# ChargerControl.net
KiCad netlist of a schematic drawn in Altium Designer
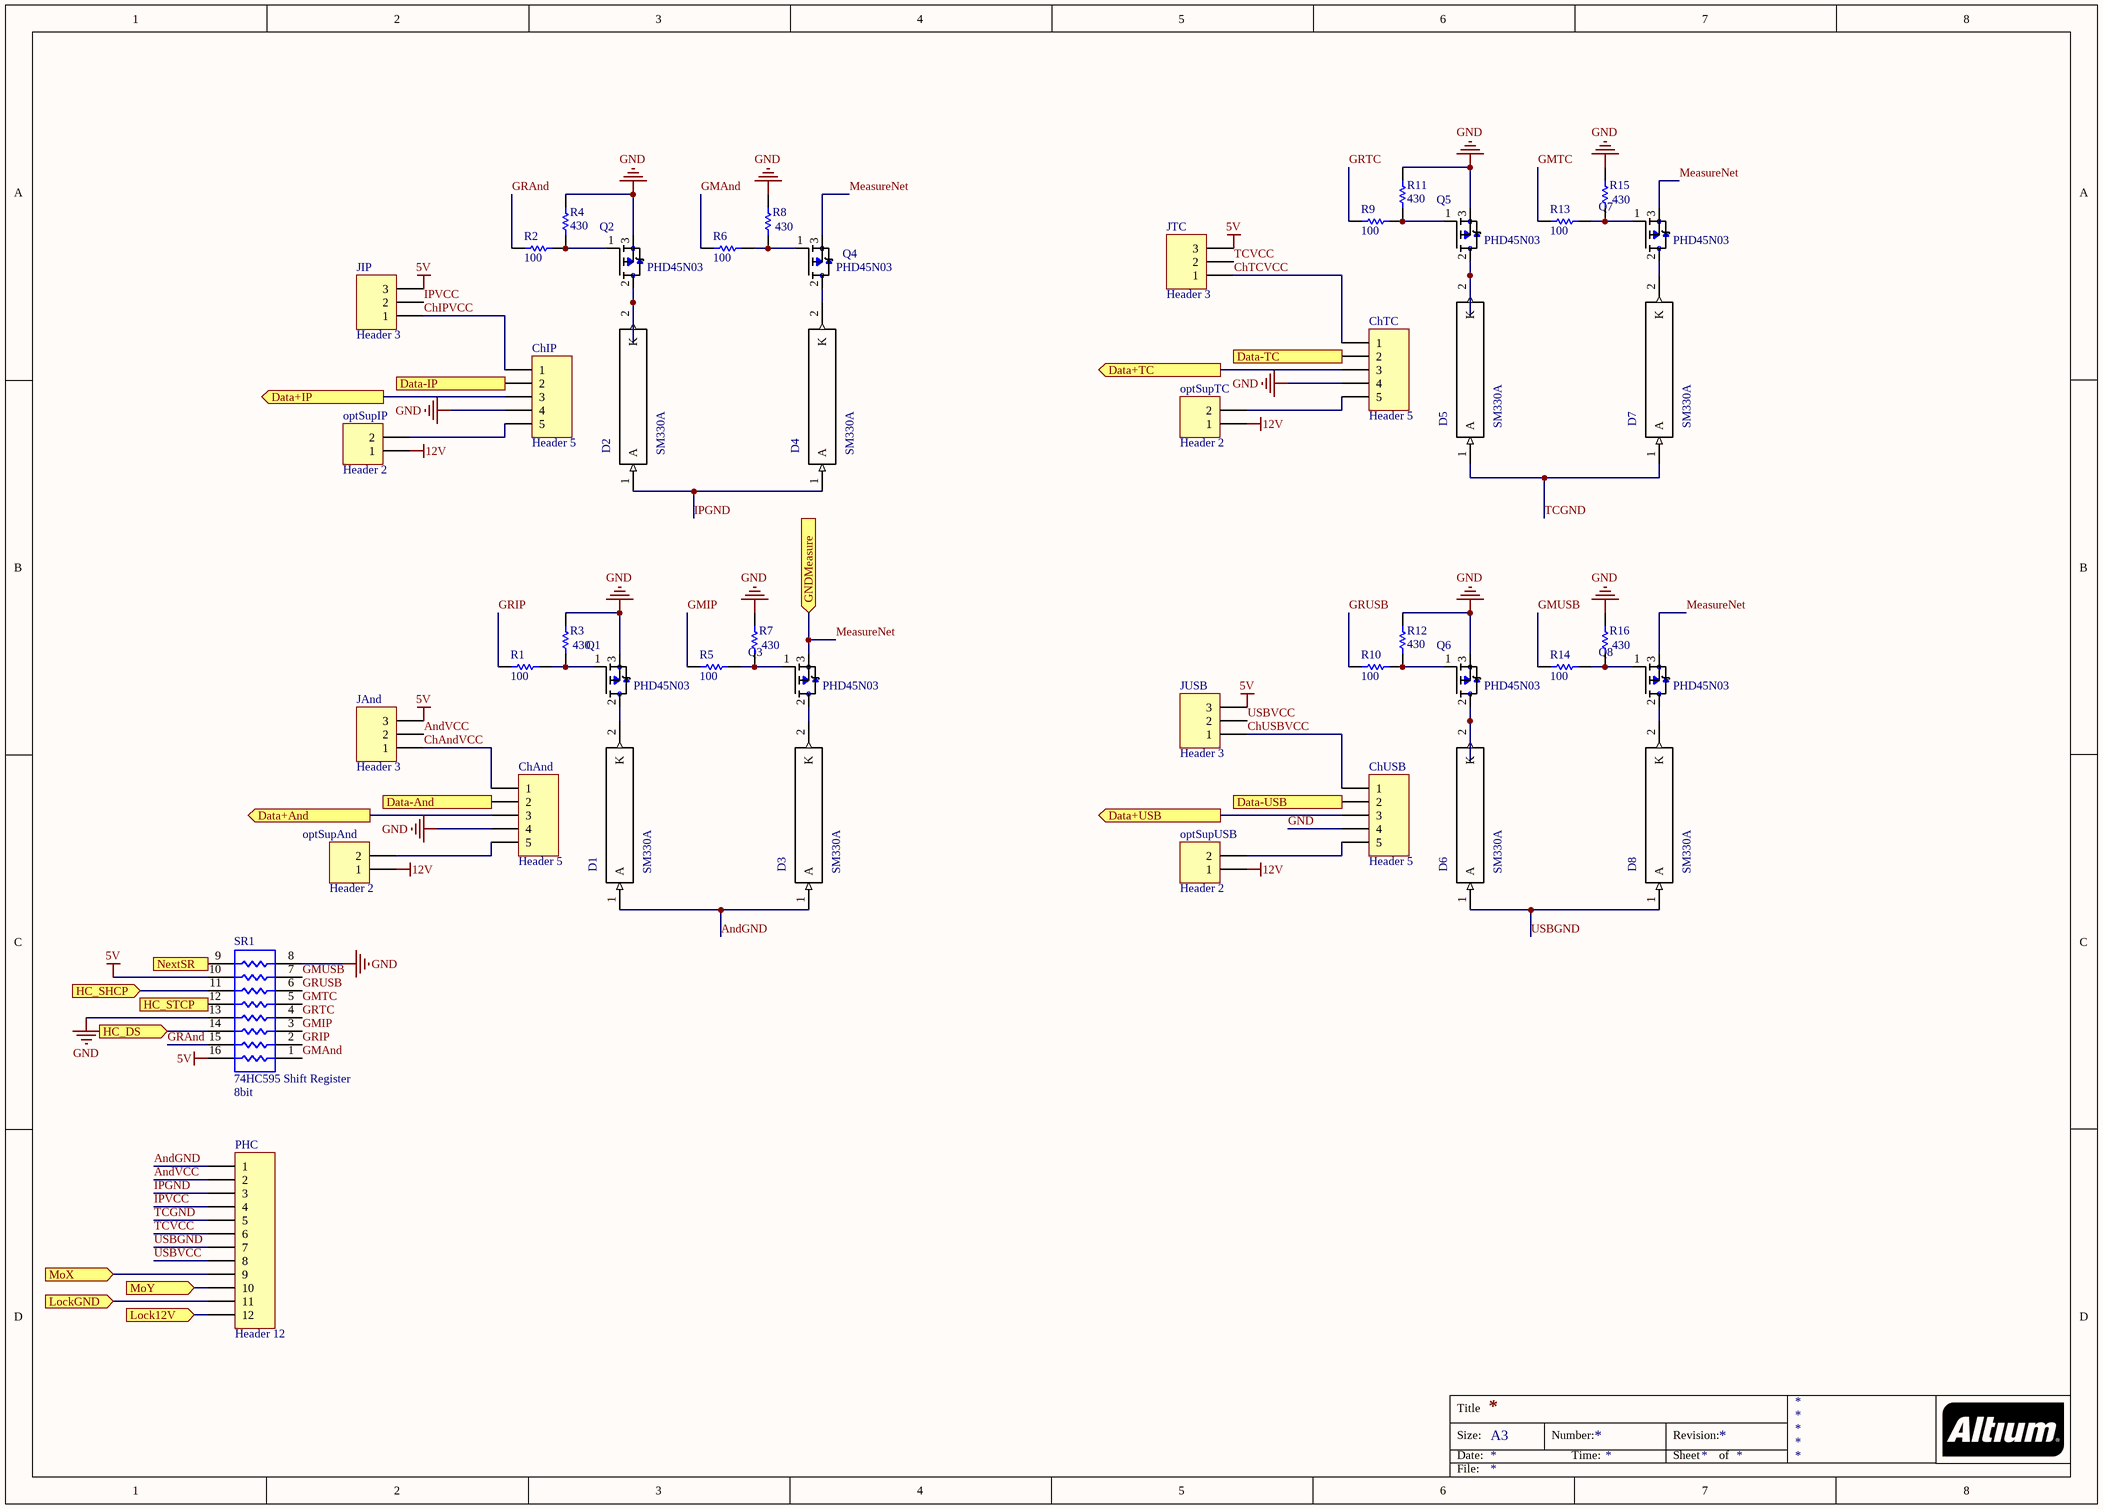
[diagram p0: ChargerControl.SchDoc]

(export (version "E")
  (design (tool "Eeschema 10.0.6"))
  (components
    (comp (ref "ChAnd")
      (value "Header 5")
      (footprint "HDR1X5")
      (description "ورودی از شارژر اندرویید")
      (fields (field (name "PUBLISHER") "Altium Limited"))
      (libsource (lib "Miscellaneous Connectors") (part "Header 5"))
    )
    (comp (ref "ChIP")
      (value "Header 5")
      (footprint "HDR1X5")
      (description "ورودی از شارژر اندرویید")
      (fields (field (name "PUBLISHER") "Altium Limited"))
      (libsource (lib "Miscellaneous Connectors") (part "Header 5"))
    )
    (comp (ref "ChTC")
      (value "Header 5")
      (footprint "HDR1X5")
      (description "ورودی از شارژر اندرویید")
      (fields (field (name "PUBLISHER") "Altium Limited"))
      (libsource (lib "Miscellaneous Connectors") (part "Header 5"))
    )
    (comp (ref "ChUSB")
      (value "Header 5")
      (footprint "HDR1X5")
      (description "ورودی از شارژر اندرویید")
      (fields (field (name "PUBLISHER") "Altium Limited"))
      (libsource (lib "Miscellaneous Connectors") (part "Header 5"))
    )
    (comp (ref "D1")
      (value "SM330A")
      (footprint "*DIOM5227X270N_S1M(Primary)")
      (description "SCHOTTKY RECTIFIER 2A; Voltage Vrrm: 60V; Diode Case Style: DO-214AC; Case Style: DO-214AC")
      (fields (field (name "MF") "STMicroelectronics") (field (name "MP") "STPS2L60A"))
      (libsource (lib "STPS2L60A") (part "STPS2L60A"))
    )
    (comp (ref "D2")
      (value "SM330A")
      (footprint "*DIOM5227X270N_S1M(Primary)")
      (description "SCHOTTKY RECTIFIER 2A; Voltage Vrrm: 60V; Diode Case Style: DO-214AC; Case Style: DO-214AC")
      (fields (field (name "MF") "STMicroelectronics") (field (name "MP") "STPS2L60A"))
      (libsource (lib "STPS2L60A") (part "STPS2L60A"))
    )
    (comp (ref "D3")
      (value "SM330A")
      (footprint "*DIOM5227X270N_S1M(Primary)")
      (description "SCHOTTKY RECTIFIER 2A; Voltage Vrrm: 60V; Diode Case Style: DO-214AC; Case Style: DO-214AC")
      (fields (field (name "MF") "STMicroelectronics") (field (name "MP") "STPS2L60A"))
      (libsource (lib "STPS2L60A") (part "STPS2L60A"))
    )
    (comp (ref "D4")
      (value "SM330A")
      (footprint "*DIOM5227X270N_S1M(Primary)")
      (description "SCHOTTKY RECTIFIER 2A; Voltage Vrrm: 60V; Diode Case Style: DO-214AC; Case Style: DO-214AC")
      (fields (field (name "MF") "STMicroelectronics") (field (name "MP") "STPS2L60A"))
      (libsource (lib "STPS2L60A") (part "STPS2L60A"))
    )
    (comp (ref "D5")
      (value "SM330A")
      (footprint "*DIOM5227X270N_S1M(Primary)")
      (description "SCHOTTKY RECTIFIER 2A; Voltage Vrrm: 60V; Diode Case Style: DO-214AC; Case Style: DO-214AC")
      (fields (field (name "MF") "STMicroelectronics") (field (name "MP") "STPS2L60A"))
      (libsource (lib "STPS2L60A") (part "STPS2L60A"))
    )
    (comp (ref "D6")
      (value "SM330A")
      (footprint "*DIOM5227X270N_S1M(Primary)")
      (description "SCHOTTKY RECTIFIER 2A; Voltage Vrrm: 60V; Diode Case Style: DO-214AC; Case Style: DO-214AC")
      (fields (field (name "MF") "STMicroelectronics") (field (name "MP") "STPS2L60A"))
      (libsource (lib "STPS2L60A") (part "STPS2L60A"))
    )
    (comp (ref "D7")
      (value "SM330A")
      (footprint "*DIOM5227X270N_S1M(Primary)")
      (description "SCHOTTKY RECTIFIER 2A; Voltage Vrrm: 60V; Diode Case Style: DO-214AC; Case Style: DO-214AC")
      (fields (field (name "MF") "STMicroelectronics") (field (name "MP") "STPS2L60A"))
      (libsource (lib "STPS2L60A") (part "STPS2L60A"))
    )
    (comp (ref "D8")
      (value "SM330A")
      (footprint "*DIOM5227X270N_S1M(Primary)")
      (description "SCHOTTKY RECTIFIER 2A; Voltage Vrrm: 60V; Diode Case Style: DO-214AC; Case Style: DO-214AC")
      (fields (field (name "MF") "STMicroelectronics") (field (name "MP") "STPS2L60A"))
      (libsource (lib "STPS2L60A") (part "STPS2L60A"))
    )
    (comp (ref "JAnd")
      (value "Header 3")
      (footprint "HDR1X3")
      (description "جامپر انتخاب بین 5 ثابت خروجی (منبع تغذیه ثابت) یا انتخاب خروجی شارژر برای قفسه")
      (fields (field (name "PUBLISHER") "Altium Limited"))
      (libsource (lib "Miscellaneous Connectors") (part "Header 3"))
    )
    (comp (ref "JIP")
      (value "Header 3")
      (footprint "HDR1X3")
      (description "جامپر انتخاب بین 5 ثابت خروجی (منبع تغذیه ثابت) یا انتخاب خروجی شارژر برای قفسه")
      (fields (field (name "PUBLISHER") "Altium Limited"))
      (libsource (lib "Miscellaneous Connectors") (part "Header 3"))
    )
    (comp (ref "JTC")
      (value "Header 3")
      (footprint "HDR1X3")
      (description "جامپر انتخاب بین 5 ثابت خروجی (منبع تغذیه ثابت) یا انتخاب خروجی شارژر برای قفسه")
      (fields (field (name "PUBLISHER") "Altium Limited"))
      (libsource (lib "Miscellaneous Connectors") (part "Header 3"))
    )
    (comp (ref "JUSB")
      (value "Header 3")
      (footprint "HDR1X3")
      (description "جامپر انتخاب بین 5 ثابت خروجی (منبع تغذیه ثابت) یا انتخاب خروجی شارژر برای قفسه")
      (fields (field (name "PUBLISHER") "Altium Limited"))
      (libsource (lib "Miscellaneous Connectors") (part "Header 3"))
    )
    (comp (ref "optSupAnd")
      (value "Header 2")
      (footprint "HDR1X2")
      (description "اگر شارژر ورودی 12 ولت داشته باشد این جامپر 12 ولت بایستی وصل شود")
      (fields (field (name "PUBLISHER") "Altium Limited"))
      (libsource (lib "Miscellaneous Connectors") (part "Header 2"))
    )
    (comp (ref "optSupIP")
      (value "Header 2")
      (footprint "HDR1X2")
      (description "اگر شارژر ورودی 12 ولت داشته باشد این جامپر 12 ولت بایستی وصل شود")
      (fields (field (name "PUBLISHER") "Altium Limited"))
      (libsource (lib "Miscellaneous Connectors") (part "Header 2"))
    )
    (comp (ref "optSupTC")
      (value "Header 2")
      (footprint "HDR1X2")
      (description "اگر شارژر ورودی 12 ولت داشته باشد این جامپر 12 ولت بایستی وصل شود")
      (fields (field (name "PUBLISHER") "Altium Limited"))
      (libsource (lib "Miscellaneous Connectors") (part "Header 2"))
    )
    (comp (ref "optSupUSB")
      (value "Header 2")
      (footprint "HDR1X2")
      (description "اگر شارژر ورودی 12 ولت داشته باشد این جامپر 12 ولت بایستی وصل شود")
      (fields (field (name "PUBLISHER") "Altium Limited"))
      (libsource (lib "Miscellaneous Connectors") (part "Header 2"))
    )
    (comp (ref "PHC")
      (value "Header 12")
      (footprint "HDR1X12")
      (description "Header, 12-Pin")
      (fields (field (name "PUBLISHER") "Altium Limited"))
      (libsource (lib "Miscellaneous Connectors") (part "Header 12"))
    )
    (comp (ref "Q1")
      (value "PHD45N03")
      (footprint "*DPAK228P998X235-3N")
      (description "P-Channel 40 V 10.6 mOhm OptiMOSآ®-P2 Power-Transistor -PG-TO-252-3")
      (fields (field (name "MP") "IPD50P04P4L-11") (field (name "MF") "Infineon Technologies"))
      (libsource (lib "IPD50P04P4L-11") (part "IPD50P04P4L-11"))
    )
    (comp (ref "Q2")
      (value "PHD45N03")
      (footprint "*DPAK228P998X235-3N")
      (description "P-Channel 40 V 10.6 mOhm OptiMOSآ®-P2 Power-Transistor -PG-TO-252-3")
      (fields (field (name "MP") "IPD50P04P4L-11") (field (name "MF") "Infineon Technologies"))
      (libsource (lib "IPD50P04P4L-11") (part "IPD50P04P4L-11"))
    )
    (comp (ref "Q3")
      (value "PHD45N03")
      (footprint "*DPAK228P998X235-3N")
      (description "P-Channel 40 V 10.6 mOhm OptiMOSآ®-P2 Power-Transistor -PG-TO-252-3")
      (fields (field (name "MP") "IPD50P04P4L-11") (field (name "MF") "Infineon Technologies"))
      (libsource (lib "IPD50P04P4L-11") (part "IPD50P04P4L-11"))
    )
    (comp (ref "Q4")
      (value "PHD45N03")
      (footprint "*DPAK228P998X235-3N")
      (description "P-Channel 40 V 10.6 mOhm OptiMOSآ®-P2 Power-Transistor -PG-TO-252-3")
      (fields (field (name "MP") "IPD50P04P4L-11") (field (name "MF") "Infineon Technologies"))
      (libsource (lib "IPD50P04P4L-11") (part "IPD50P04P4L-11"))
    )
    (comp (ref "Q5")
      (value "PHD45N03")
      (footprint "*DPAK228P998X235-3N")
      (description "P-Channel 40 V 10.6 mOhm OptiMOSآ®-P2 Power-Transistor -PG-TO-252-3")
      (fields (field (name "MP") "IPD50P04P4L-11") (field (name "MF") "Infineon Technologies"))
      (libsource (lib "IPD50P04P4L-11") (part "IPD50P04P4L-11"))
    )
    (comp (ref "Q6")
      (value "PHD45N03")
      (footprint "*DPAK228P998X235-3N")
      (description "P-Channel 40 V 10.6 mOhm OptiMOSآ®-P2 Power-Transistor -PG-TO-252-3")
      (fields (field (name "MP") "IPD50P04P4L-11") (field (name "MF") "Infineon Technologies"))
      (libsource (lib "IPD50P04P4L-11") (part "IPD50P04P4L-11"))
    )
    (comp (ref "Q7")
      (value "PHD45N03")
      (footprint "*DPAK228P998X235-3N")
      (description "P-Channel 40 V 10.6 mOhm OptiMOSآ®-P2 Power-Transistor -PG-TO-252-3")
      (fields (field (name "MP") "IPD50P04P4L-11") (field (name "MF") "Infineon Technologies"))
      (libsource (lib "IPD50P04P4L-11") (part "IPD50P04P4L-11"))
    )
    (comp (ref "Q8")
      (value "PHD45N03")
      (footprint "*DPAK228P998X235-3N")
      (description "P-Channel 40 V 10.6 mOhm OptiMOSآ®-P2 Power-Transistor -PG-TO-252-3")
      (fields (field (name "MP") "IPD50P04P4L-11") (field (name "MF") "Infineon Technologies"))
      (libsource (lib "IPD50P04P4L-11") (part "IPD50P04P4L-11"))
    )
    (comp (ref "R1")
      (value "100")
      (footprint "6-0805_L")
      (description "Resistor")
      (fields (field (name "Comment") "R100") (field (name "PUBLISHER") "Altium Limited"))
      (libsource (lib "Miscellaneous Devices") (part "Res1"))
    )
    (comp (ref "R2")
      (value "100")
      (footprint "6-0805_L")
      (description "Resistor")
      (fields (field (name "Comment") "R100") (field (name "PUBLISHER") "Altium Limited"))
      (libsource (lib "Miscellaneous Devices") (part "Res1"))
    )
    (comp (ref "R3")
      (value "430")
      (footprint "6-0805_L")
      (description "Resistor")
      (fields (field (name "Comment") "R430") (field (name "PUBLISHER") "Altium Limited"))
      (libsource (lib "Miscellaneous Devices") (part "Res1"))
    )
    (comp (ref "R4")
      (value "430")
      (footprint "6-0805_L")
      (description "Resistor")
      (fields (field (name "Comment") "R430") (field (name "PUBLISHER") "Altium Limited"))
      (libsource (lib "Miscellaneous Devices") (part "Res1"))
    )
    (comp (ref "R5")
      (value "100")
      (footprint "6-0805_L")
      (description "Resistor")
      (fields (field (name "Comment") "R100") (field (name "PUBLISHER") "Altium Limited"))
      (libsource (lib "Miscellaneous Devices") (part "Res1"))
    )
    (comp (ref "R6")
      (value "100")
      (footprint "6-0805_L")
      (description "Resistor")
      (fields (field (name "Comment") "R100") (field (name "PUBLISHER") "Altium Limited"))
      (libsource (lib "Miscellaneous Devices") (part "Res1"))
    )
    (comp (ref "R7")
      (value "430")
      (footprint "6-0805_L")
      (description "Resistor")
      (fields (field (name "Comment") "R430") (field (name "PUBLISHER") "Altium Limited"))
      (libsource (lib "Miscellaneous Devices") (part "Res1"))
    )
    (comp (ref "R8")
      (value "430")
      (footprint "6-0805_L")
      (description "Resistor")
      (fields (field (name "Comment") "R430") (field (name "PUBLISHER") "Altium Limited"))
      (libsource (lib "Miscellaneous Devices") (part "Res1"))
    )
    (comp (ref "R9")
      (value "100")
      (footprint "6-0805_L")
      (description "Resistor")
      (fields (field (name "Comment") "R100") (field (name "PUBLISHER") "Altium Limited"))
      (libsource (lib "Miscellaneous Devices") (part "Res1"))
    )
    (comp (ref "R10")
      (value "100")
      (footprint "6-0805_L")
      (description "Resistor")
      (fields (field (name "Comment") "R100") (field (name "PUBLISHER") "Altium Limited"))
      (libsource (lib "Miscellaneous Devices") (part "Res1"))
    )
    (comp (ref "R11")
      (value "430")
      (footprint "6-0805_L")
      (description "Resistor")
      (fields (field (name "Comment") "R430") (field (name "PUBLISHER") "Altium Limited"))
      (libsource (lib "Miscellaneous Devices") (part "Res1"))
    )
    (comp (ref "R12")
      (value "430")
      (footprint "6-0805_L")
      (description "Resistor")
      (fields (field (name "Comment") "R430") (field (name "PUBLISHER") "Altium Limited"))
      (libsource (lib "Miscellaneous Devices") (part "Res1"))
    )
    (comp (ref "R13")
      (value "100")
      (footprint "6-0805_L")
      (description "Resistor")
      (fields (field (name "Comment") "R100") (field (name "PUBLISHER") "Altium Limited"))
      (libsource (lib "Miscellaneous Devices") (part "Res1"))
    )
    (comp (ref "R14")
      (value "100")
      (footprint "6-0805_L")
      (description "Resistor")
      (fields (field (name "Comment") "R100") (field (name "PUBLISHER") "Altium Limited"))
      (libsource (lib "Miscellaneous Devices") (part "Res1"))
    )
    (comp (ref "R15")
      (value "430")
      (footprint "6-0805_L")
      (description "Resistor")
      (fields (field (name "Comment") "R430") (field (name "PUBLISHER") "Altium Limited"))
      (libsource (lib "Miscellaneous Devices") (part "Res1"))
    )
    (comp (ref "R16")
      (value "430")
      (footprint "6-0805_L")
      (description "Resistor")
      (fields (field (name "Comment") "R430") (field (name "PUBLISHER") "Altium Limited"))
      (libsource (lib "Miscellaneous Devices") (part "Res1"))
    )
    (comp (ref "SR1")
      (value "74HC595 Shift Register")
      (footprint "SO-16_L")
      (description "Isolated Resistor Network")
      (fields (field (name "ALTIUM_VALUE") "8bit") (field (name "PUBLISHER") "Altium Limited"))
      (libsource (lib "Miscellaneous Devices") (part "Res Pack3"))
    )
  )
  (nets
    (net (code "1") (name "/AndGND") (class "Default")
      (node (ref "D1") (pin "1") (pinfunction "A_1") (pintype "input"))
      (node (ref "D3") (pin "1") (pinfunction "A_1") (pintype "input"))
      (node (ref "PHC") (pin "1") (pinfunction "1_1") (pintype "passive"))
    )
    (net (code "2") (name "/AndVCC") (class "Default")
      (node (ref "JAnd") (pin "2") (pinfunction "2_2") (pintype "passive"))
      (node (ref "PHC") (pin "2") (pinfunction "2_2") (pintype "passive"))
    )
    (net (code "3") (name "/ChAndVCC") (class "Default")
      (node (ref "ChAnd") (pin "1") (pinfunction "1_1") (pintype "passive"))
      (node (ref "JAnd") (pin "1") (pinfunction "1_1") (pintype "passive"))
    )
    (net (code "4") (name "/ChIPVCC") (class "Default")
      (node (ref "ChIP") (pin "1") (pinfunction "1_1") (pintype "passive"))
      (node (ref "JIP") (pin "1") (pinfunction "1_1") (pintype "passive"))
    )
    (net (code "5") (name "/ChTCVCC") (class "Default")
      (node (ref "ChTC") (pin "1") (pinfunction "1_1") (pintype "passive"))
      (node (ref "JTC") (pin "1") (pinfunction "1_1") (pintype "passive"))
    )
    (net (code "6") (name "/ChUSBVCC") (class "Default")
      (node (ref "ChUSB") (pin "1") (pinfunction "1_1") (pintype "passive"))
      (node (ref "JUSB") (pin "1") (pinfunction "1_1") (pintype "passive"))
    )
    (net (code "7") (name "/Data+And") (class "Default")
      (node (ref "ChAnd") (pin "3") (pinfunction "3_3") (pintype "passive"))
    )
    (net (code "8") (name "/Data+IP") (class "Default")
      (node (ref "ChIP") (pin "3") (pinfunction "3_3") (pintype "passive"))
    )
    (net (code "9") (name "/Data+TC") (class "Default")
      (node (ref "ChTC") (pin "3") (pinfunction "3_3") (pintype "passive"))
    )
    (net (code "10") (name "/Data+USB") (class "Default")
      (node (ref "ChUSB") (pin "3") (pinfunction "3_3") (pintype "passive"))
    )
    (net (code "11") (name "/Data-And") (class "Default")
      (node (ref "ChAnd") (pin "2") (pinfunction "2_2") (pintype "passive"))
    )
    (net (code "12") (name "/Data-IP") (class "Default")
      (node (ref "ChIP") (pin "2") (pinfunction "2_2") (pintype "passive"))
    )
    (net (code "13") (name "/Data-TC") (class "Default")
      (node (ref "ChTC") (pin "2") (pinfunction "2_2") (pintype "passive"))
    )
    (net (code "14") (name "/Data-USB") (class "Default")
      (node (ref "ChUSB") (pin "2") (pinfunction "2_2") (pintype "passive"))
    )
    (net (code "15") (name "/GMAnd") (class "Default")
      (node (ref "R6") (pin "1") (pinfunction "1_1") (pintype "passive"))
      (node (ref "SR1") (pin "1") (pinfunction "1_1") (pintype "passive"))
    )
    (net (code "16") (name "/GMIP") (class "Default")
      (node (ref "R5") (pin "1") (pinfunction "1_1") (pintype "passive"))
      (node (ref "SR1") (pin "3") (pinfunction "3_3") (pintype "passive"))
    )
    (net (code "17") (name "/GMTC") (class "Default")
      (node (ref "R13") (pin "1") (pinfunction "1_1") (pintype "passive"))
      (node (ref "SR1") (pin "5") (pinfunction "5_5") (pintype "passive"))
    )
    (net (code "18") (name "/GMUSB") (class "Default")
      (node (ref "R14") (pin "1") (pinfunction "1_1") (pintype "passive"))
      (node (ref "SR1") (pin "7") (pinfunction "7_7") (pintype "passive"))
    )
    (net (code "19") (name "/GRAnd") (class "Default")
      (node (ref "R2") (pin "1") (pinfunction "1_1") (pintype "passive"))
      (node (ref "SR1") (pin "15") (pinfunction "15_15") (pintype "passive"))
    )
    (net (code "20") (name "/GRIP") (class "Default")
      (node (ref "R1") (pin "1") (pinfunction "1_1") (pintype "passive"))
      (node (ref "SR1") (pin "2") (pinfunction "2_2") (pintype "passive"))
    )
    (net (code "21") (name "/GRTC") (class "Default")
      (node (ref "R9") (pin "1") (pinfunction "1_1") (pintype "passive"))
      (node (ref "SR1") (pin "4") (pinfunction "4_4") (pintype "passive"))
    )
    (net (code "22") (name "/GRUSB") (class "Default")
      (node (ref "R10") (pin "1") (pinfunction "1_1") (pintype "passive"))
      (node (ref "SR1") (pin "6") (pinfunction "6_6") (pintype "passive"))
    )
    (net (code "23") (name "/HC_DS") (class "Default")
      (node (ref "SR1") (pin "14") (pinfunction "14_14") (pintype "passive"))
    )
    (net (code "24") (name "/HC_SHCP") (class "Default")
      (node (ref "SR1") (pin "11") (pinfunction "11_11") (pintype "passive"))
    )
    (net (code "25") (name "/HC_STCP") (class "Default")
      (node (ref "SR1") (pin "12") (pinfunction "12_12") (pintype "passive"))
    )
    (net (code "26") (name "/IPGND") (class "Default")
      (node (ref "D2") (pin "1") (pinfunction "A_1") (pintype "input"))
      (node (ref "D4") (pin "1") (pinfunction "A_1") (pintype "input"))
      (node (ref "PHC") (pin "3") (pinfunction "3_3") (pintype "passive"))
    )
    (net (code "27") (name "/IPVCC") (class "Default")
      (node (ref "JIP") (pin "2") (pinfunction "2_2") (pintype "passive"))
      (node (ref "PHC") (pin "4") (pinfunction "4_4") (pintype "passive"))
    )
    (net (code "28") (name "/Lock12V") (class "Default")
      (node (ref "PHC") (pin "12") (pinfunction "12_12") (pintype "passive"))
    )
    (net (code "29") (name "/LockGND") (class "Default")
      (node (ref "PHC") (pin "11") (pinfunction "11_11") (pintype "passive"))
    )
    (net (code "30") (name "/MeasureNet") (class "Default")
      (node (ref "Q3") (pin "3") (pinfunction "S_3") (pintype "passive"))
      (node (ref "Q4") (pin "3") (pinfunction "S_3") (pintype "passive"))
      (node (ref "Q7") (pin "3") (pinfunction "S_3") (pintype "passive"))
      (node (ref "Q8") (pin "3") (pinfunction "S_3") (pintype "passive"))
    )
    (net (code "31") (name "/MoX") (class "Default")
      (node (ref "PHC") (pin "9") (pinfunction "9_9") (pintype "passive"))
    )
    (net (code "32") (name "/MoY") (class "Default")
      (node (ref "PHC") (pin "10") (pinfunction "10_10") (pintype "passive"))
    )
    (net (code "33") (name "/NextSR") (class "Default")
      (node (ref "SR1") (pin "9") (pinfunction "9_9") (pintype "passive"))
    )
    (net (code "34") (name "/TCGND") (class "Default")
      (node (ref "D5") (pin "1") (pinfunction "A_1") (pintype "input"))
      (node (ref "D7") (pin "1") (pinfunction "A_1") (pintype "input"))
      (node (ref "PHC") (pin "5") (pinfunction "5_5") (pintype "passive"))
    )
    (net (code "35") (name "/TCVCC") (class "Default")
      (node (ref "JTC") (pin "2") (pinfunction "2_2") (pintype "passive"))
      (node (ref "PHC") (pin "6") (pinfunction "6_6") (pintype "passive"))
    )
    (net (code "36") (name "/USBGND") (class "Default")
      (node (ref "D6") (pin "1") (pinfunction "A_1") (pintype "input"))
      (node (ref "D8") (pin "1") (pinfunction "A_1") (pintype "input"))
      (node (ref "PHC") (pin "7") (pinfunction "7_7") (pintype "passive"))
    )
    (net (code "37") (name "/USBVCC") (class "Default")
      (node (ref "JUSB") (pin "2") (pinfunction "2_2") (pintype "passive"))
      (node (ref "PHC") (pin "8") (pinfunction "8_8") (pintype "passive"))
    )
    (net (code "38") (name "5V") (class "Default")
      (node (ref "JAnd") (pin "3") (pinfunction "3_3") (pintype "passive"))
      (node (ref "JIP") (pin "3") (pinfunction "3_3") (pintype "passive"))
      (node (ref "JTC") (pin "3") (pinfunction "3_3") (pintype "passive"))
      (node (ref "JUSB") (pin "3") (pinfunction "3_3") (pintype "passive"))
      (node (ref "SR1") (pin "10") (pinfunction "10_10") (pintype "passive"))
      (node (ref "SR1") (pin "16") (pinfunction "16_16") (pintype "passive"))
    )
    (net (code "39") (name "12V") (class "Default")
      (node (ref "optSupAnd") (pin "1") (pinfunction "1_1") (pintype "passive"))
      (node (ref "optSupIP") (pin "1") (pinfunction "1_1") (pintype "passive"))
      (node (ref "optSupTC") (pin "1") (pinfunction "1_1") (pintype "passive"))
      (node (ref "optSupUSB") (pin "1") (pinfunction "1_1") (pintype "passive"))
    )
    (net (code "40") (name "GND") (class "Default")
      (node (ref "ChAnd") (pin "4") (pinfunction "4_4") (pintype "passive"))
      (node (ref "ChIP") (pin "4") (pinfunction "4_4") (pintype "passive"))
      (node (ref "ChTC") (pin "4") (pinfunction "4_4") (pintype "passive"))
      (node (ref "ChUSB") (pin "4") (pinfunction "4_4") (pintype "passive"))
      (node (ref "Q1") (pin "3") (pinfunction "S_3") (pintype "passive"))
      (node (ref "Q2") (pin "3") (pinfunction "S_3") (pintype "passive"))
      (node (ref "Q5") (pin "3") (pinfunction "S_3") (pintype "passive"))
      (node (ref "Q6") (pin "3") (pinfunction "S_3") (pintype "passive"))
      (node (ref "R11") (pin "1") (pinfunction "1_1") (pintype "passive"))
      (node (ref "R12") (pin "1") (pinfunction "1_1") (pintype "passive"))
      (node (ref "R15") (pin "1") (pinfunction "1_1") (pintype "passive"))
      (node (ref "R16") (pin "1") (pinfunction "1_1") (pintype "passive"))
      (node (ref "R3") (pin "1") (pinfunction "1_1") (pintype "passive"))
      (node (ref "R4") (pin "1") (pinfunction "1_1") (pintype "passive"))
      (node (ref "R7") (pin "1") (pinfunction "1_1") (pintype "passive"))
      (node (ref "R8") (pin "1") (pinfunction "1_1") (pintype "passive"))
      (node (ref "SR1") (pin "13") (pinfunction "13_13") (pintype "passive"))
      (node (ref "SR1") (pin "8") (pinfunction "8_8") (pintype "passive"))
    )
    (net (code "41") (name "Net-(ChAnd-Pad5)") (class "Default")
      (node (ref "ChAnd") (pin "5") (pinfunction "5_5") (pintype "passive"))
      (node (ref "optSupAnd") (pin "2") (pinfunction "2_2") (pintype "passive"))
    )
    (net (code "42") (name "Net-(ChIP-Pad5)") (class "Default")
      (node (ref "ChIP") (pin "5") (pinfunction "5_5") (pintype "passive"))
      (node (ref "optSupIP") (pin "2") (pinfunction "2_2") (pintype "passive"))
    )
    (net (code "43") (name "Net-(ChTC-Pad5)") (class "Default")
      (node (ref "ChTC") (pin "5") (pinfunction "5_5") (pintype "passive"))
      (node (ref "optSupTC") (pin "2") (pinfunction "2_2") (pintype "passive"))
    )
    (net (code "44") (name "Net-(ChUSB-Pad5)") (class "Default")
      (node (ref "ChUSB") (pin "5") (pinfunction "5_5") (pintype "passive"))
      (node (ref "optSupUSB") (pin "2") (pinfunction "2_2") (pintype "passive"))
    )
    (net (code "45") (name "Net-(D1-K)") (class "Default")
      (node (ref "D1") (pin "2") (pinfunction "K_2") (pintype "output"))
      (node (ref "Q1") (pin "2") (pinfunction "D_2") (pintype "passive"))
    )
    (net (code "46") (name "Net-(D2-K)") (class "Default")
      (node (ref "D2") (pin "2") (pinfunction "K_2") (pintype "output"))
      (node (ref "Q2") (pin "2") (pinfunction "D_2") (pintype "passive"))
    )
    (net (code "47") (name "Net-(D3-K)") (class "Default")
      (node (ref "D3") (pin "2") (pinfunction "K_2") (pintype "output"))
      (node (ref "Q3") (pin "2") (pinfunction "D_2") (pintype "passive"))
    )
    (net (code "48") (name "Net-(D4-K)") (class "Default")
      (node (ref "D4") (pin "2") (pinfunction "K_2") (pintype "output"))
      (node (ref "Q4") (pin "2") (pinfunction "D_2") (pintype "passive"))
    )
    (net (code "49") (name "Net-(D5-K)") (class "Default")
      (node (ref "D5") (pin "2") (pinfunction "K_2") (pintype "output"))
      (node (ref "Q5") (pin "2") (pinfunction "D_2") (pintype "passive"))
    )
    (net (code "50") (name "Net-(D6-K)") (class "Default")
      (node (ref "D6") (pin "2") (pinfunction "K_2") (pintype "output"))
      (node (ref "Q6") (pin "2") (pinfunction "D_2") (pintype "passive"))
    )
    (net (code "51") (name "Net-(D7-K)") (class "Default")
      (node (ref "D7") (pin "2") (pinfunction "K_2") (pintype "output"))
      (node (ref "Q7") (pin "2") (pinfunction "D_2") (pintype "passive"))
    )
    (net (code "52") (name "Net-(D8-K)") (class "Default")
      (node (ref "D8") (pin "2") (pinfunction "K_2") (pintype "output"))
      (node (ref "Q8") (pin "2") (pinfunction "D_2") (pintype "passive"))
    )
    (net (code "53") (name "Net-(Q1-G)") (class "Default")
      (node (ref "Q1") (pin "1") (pinfunction "G_1") (pintype "passive"))
      (node (ref "R1") (pin "2") (pinfunction "2_2") (pintype "passive"))
      (node (ref "R3") (pin "2") (pinfunction "2_2") (pintype "passive"))
    )
    (net (code "54") (name "Net-(Q2-G)") (class "Default")
      (node (ref "Q2") (pin "1") (pinfunction "G_1") (pintype "passive"))
      (node (ref "R2") (pin "2") (pinfunction "2_2") (pintype "passive"))
      (node (ref "R4") (pin "2") (pinfunction "2_2") (pintype "passive"))
    )
    (net (code "55") (name "Net-(Q3-G)") (class "Default")
      (node (ref "Q3") (pin "1") (pinfunction "G_1") (pintype "passive"))
      (node (ref "R5") (pin "2") (pinfunction "2_2") (pintype "passive"))
      (node (ref "R7") (pin "2") (pinfunction "2_2") (pintype "passive"))
    )
    (net (code "56") (name "Net-(Q4-G)") (class "Default")
      (node (ref "Q4") (pin "1") (pinfunction "G_1") (pintype "passive"))
      (node (ref "R6") (pin "2") (pinfunction "2_2") (pintype "passive"))
      (node (ref "R8") (pin "2") (pinfunction "2_2") (pintype "passive"))
    )
    (net (code "57") (name "Net-(Q5-G)") (class "Default")
      (node (ref "Q5") (pin "1") (pinfunction "G_1") (pintype "passive"))
      (node (ref "R11") (pin "2") (pinfunction "2_2") (pintype "passive"))
      (node (ref "R9") (pin "2") (pinfunction "2_2") (pintype "passive"))
    )
    (net (code "58") (name "Net-(Q6-G)") (class "Default")
      (node (ref "Q6") (pin "1") (pinfunction "G_1") (pintype "passive"))
      (node (ref "R10") (pin "2") (pinfunction "2_2") (pintype "passive"))
      (node (ref "R12") (pin "2") (pinfunction "2_2") (pintype "passive"))
    )
    (net (code "59") (name "Net-(Q7-G)") (class "Default")
      (node (ref "Q7") (pin "1") (pinfunction "G_1") (pintype "passive"))
      (node (ref "R13") (pin "2") (pinfunction "2_2") (pintype "passive"))
      (node (ref "R15") (pin "2") (pinfunction "2_2") (pintype "passive"))
    )
    (net (code "60") (name "Net-(Q8-G)") (class "Default")
      (node (ref "Q8") (pin "1") (pinfunction "G_1") (pintype "passive"))
      (node (ref "R14") (pin "2") (pinfunction "2_2") (pintype "passive"))
      (node (ref "R16") (pin "2") (pinfunction "2_2") (pintype "passive"))
    )
  )
)
